# DriverBoard.net
KiCad netlist of a schematic drawn in Altium Designer
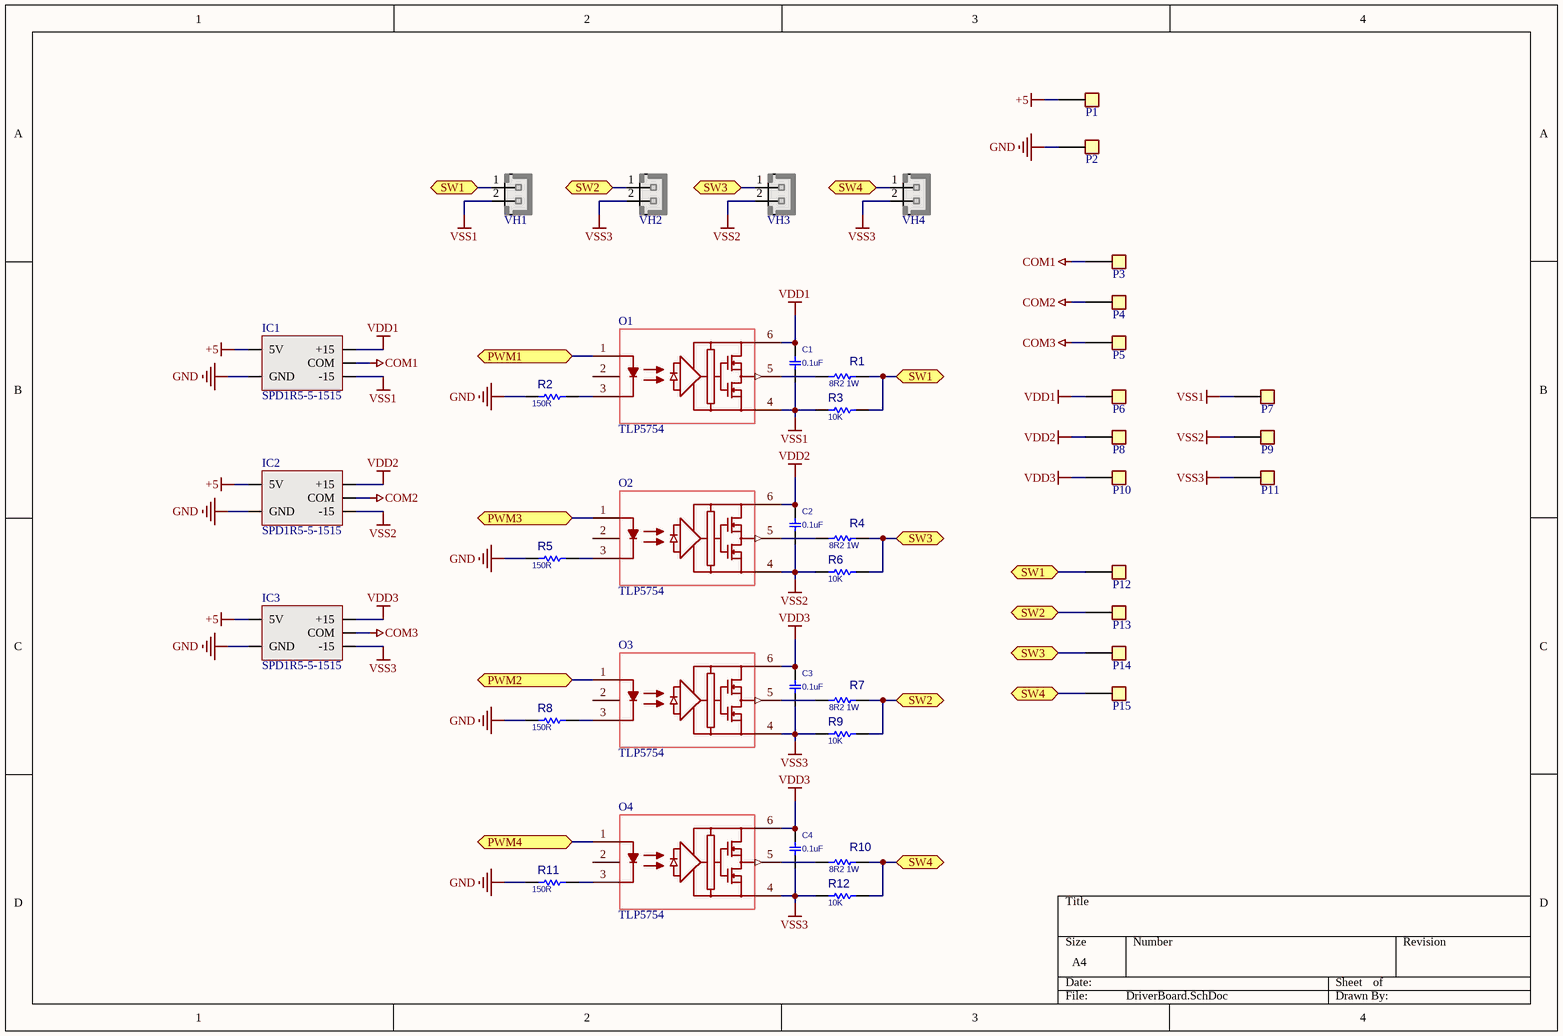
[diagram p0: DriverBoard.SchDoc]

(export (version "E")
  (design (tool "Eeschema 10.0.6"))
  (components
    (comp (ref "C1")
      (value "0.1uF")
      (footprint "cap_0805")
      (description "CAP SMD")
      (fields (field (name "MANF_P#") "MANF_PART#"))
      (libsource (lib "IoT") (part "CAP SMD"))
    )
    (comp (ref "C2")
      (value "0.1uF")
      (footprint "cap_0805")
      (description "CAP SMD")
      (fields (field (name "MANF_P#") "MANF_PART#"))
      (libsource (lib "IoT") (part "CAP SMD"))
    )
    (comp (ref "C3")
      (value "0.1uF")
      (footprint "cap_0805")
      (description "CAP SMD")
      (fields (field (name "MANF_P#") "MANF_PART#"))
      (libsource (lib "IoT") (part "CAP SMD"))
    )
    (comp (ref "C4")
      (value "0.1uF")
      (footprint "cap_0805")
      (description "CAP SMD")
      (fields (field (name "MANF_P#") "MANF_PART#"))
      (libsource (lib "IoT") (part "CAP SMD"))
    )
    (comp (ref "IC1")
      (value "SPD1R5-5-1515")
      (footprint "SPS1R5")
      (description "Power supply Driver SPD1R5-5-1515\r\nEfficiency 80%\r\nInput 0.381A\r\nOutput 50mA")
      (libsource (lib "IoT") (part "SPD1R5-5-1515"))
    )
    (comp (ref "IC2")
      (value "SPD1R5-5-1515")
      (footprint "SPS1R5")
      (description "Power supply Driver SPD1R5-5-1515\r\nEfficiency 80%\r\nInput 0.381A\r\nOutput 50mA")
      (libsource (lib "IoT") (part "SPD1R5-5-1515"))
    )
    (comp (ref "IC3")
      (value "SPD1R5-5-1515")
      (footprint "SPS1R5")
      (description "Power supply Driver SPD1R5-5-1515\r\nEfficiency 80%\r\nInput 0.381A\r\nOutput 50mA")
      (libsource (lib "IoT") (part "SPD1R5-5-1515"))
    )
    (comp (ref "O1")
      (value "TLP5754")
      (footprint "TLP5754")
      (fields (field (name "MF") "Toshiba Semiconductor") (field (name "MP") "TLP250"))
      (libsource (lib "IoT") (part "TLP5754"))
    )
    (comp (ref "O2")
      (value "TLP5754")
      (footprint "TLP5754")
      (fields (field (name "MF") "Toshiba Semiconductor") (field (name "MP") "TLP250"))
      (libsource (lib "IoT") (part "TLP5754"))
    )
    (comp (ref "O3")
      (value "TLP5754")
      (footprint "TLP5754")
      (fields (field (name "MF") "Toshiba Semiconductor") (field (name "MP") "TLP250"))
      (libsource (lib "IoT") (part "TLP5754"))
    )
    (comp (ref "O4")
      (value "TLP5754")
      (footprint "TLP5754")
      (fields (field (name "MF") "Toshiba Semiconductor") (field (name "MP") "TLP250"))
      (libsource (lib "IoT") (part "TLP5754"))
    )
    (comp (ref "P1")
      (value "test PCB")
      (footprint "tp_red_1p")
      (description "testpin")
      (libsource (lib "IoT") (part "test PCB"))
    )
    (comp (ref "P2")
      (value "test PCB")
      (footprint "Tp_black_1p")
      (description "testpin")
      (libsource (lib "IoT") (part "test PCB"))
    )
    (comp (ref "P3")
      (value "test PCB")
      (footprint "tp_white_1p")
      (description "testpin")
      (libsource (lib "IoT") (part "test PCB"))
    )
    (comp (ref "P4")
      (value "test PCB")
      (footprint "tp_white_1p")
      (description "testpin")
      (libsource (lib "IoT") (part "test PCB"))
    )
    (comp (ref "P5")
      (value "test PCB")
      (footprint "tp_white_1p")
      (description "testpin")
      (libsource (lib "IoT") (part "test PCB"))
    )
    (comp (ref "P6")
      (value "test PCB")
      (footprint "tp_red_1p")
      (description "testpin")
      (libsource (lib "IoT") (part "test PCB"))
    )
    (comp (ref "P7")
      (value "test PCB")
      (footprint "Tp_black_1p")
      (description "testpin")
      (libsource (lib "IoT") (part "test PCB"))
    )
    (comp (ref "P8")
      (value "test PCB")
      (footprint "tp_red_1p")
      (description "testpin")
      (libsource (lib "IoT") (part "test PCB"))
    )
    (comp (ref "P9")
      (value "test PCB")
      (footprint "Tp_black_1p")
      (description "testpin")
      (libsource (lib "IoT") (part "test PCB"))
    )
    (comp (ref "P10")
      (value "test PCB")
      (footprint "tp_red_1p")
      (description "testpin")
      (libsource (lib "IoT") (part "test PCB"))
    )
    (comp (ref "P11")
      (value "test PCB")
      (footprint "Tp_black_1p")
      (description "testpin")
      (libsource (lib "IoT") (part "test PCB"))
    )
    (comp (ref "P12")
      (value "test PCB")
      (footprint "Tp_blue_1p")
      (description "testpin")
      (libsource (lib "IoT") (part "test PCB"))
    )
    (comp (ref "P13")
      (value "test PCB")
      (footprint "Tp_blue_1p")
      (description "testpin")
      (libsource (lib "IoT") (part "test PCB"))
    )
    (comp (ref "P14")
      (value "test PCB")
      (footprint "Tp_blue_1p")
      (description "testpin")
      (libsource (lib "IoT") (part "test PCB"))
    )
    (comp (ref "P15")
      (value "test PCB")
      (footprint "Tp_blue_1p")
      (description "testpin")
      (libsource (lib "IoT") (part "test PCB"))
    )
    (comp (ref "R1")
      (value "8R2 1W")
      (footprint "R2512")
      (description "RES SMD")
      (fields (field (name "MANF_P#") "WSLP0805R0100FEA") (field (name "MANF") "VISHAY"))
      (libsource (lib "IoT") (part "RES SMD"))
    )
    (comp (ref "R2")
      (value "150R")
      (footprint "R0805")
      (description "RES SMD")
      (fields (field (name "MANF_P#") "WSLP0805R0100FEA") (field (name "MANF") "VISHAY"))
      (libsource (lib "IoT") (part "RES SMD"))
    )
    (comp (ref "R3")
      (value "10K")
      (footprint "R0805")
      (description "RES SMD")
      (fields (field (name "MANF_P#") "WSLP0805R0100FEA") (field (name "MANF") "VISHAY"))
      (libsource (lib "IoT") (part "RES SMD"))
    )
    (comp (ref "R4")
      (value "8R2 1W")
      (footprint "R2512")
      (description "RES SMD")
      (fields (field (name "MANF_P#") "WSLP0805R0100FEA") (field (name "MANF") "VISHAY"))
      (libsource (lib "IoT") (part "RES SMD"))
    )
    (comp (ref "R5")
      (value "150R")
      (footprint "R0805")
      (description "RES SMD")
      (fields (field (name "MANF_P#") "WSLP0805R0100FEA") (field (name "MANF") "VISHAY"))
      (libsource (lib "IoT") (part "RES SMD"))
    )
    (comp (ref "R6")
      (value "10K")
      (footprint "R0805")
      (description "RES SMD")
      (fields (field (name "MANF_P#") "WSLP0805R0100FEA") (field (name "MANF") "VISHAY"))
      (libsource (lib "IoT") (part "RES SMD"))
    )
    (comp (ref "R7")
      (value "8R2 1W")
      (footprint "R2512")
      (description "RES SMD")
      (fields (field (name "MANF_P#") "WSLP0805R0100FEA") (field (name "MANF") "VISHAY"))
      (libsource (lib "IoT") (part "RES SMD"))
    )
    (comp (ref "R8")
      (value "150R")
      (footprint "R0805")
      (description "RES SMD")
      (fields (field (name "MANF_P#") "WSLP0805R0100FEA") (field (name "MANF") "VISHAY"))
      (libsource (lib "IoT") (part "RES SMD"))
    )
    (comp (ref "R9")
      (value "10K")
      (footprint "R0805")
      (description "RES SMD")
      (fields (field (name "MANF_P#") "WSLP0805R0100FEA") (field (name "MANF") "VISHAY"))
      (libsource (lib "IoT") (part "RES SMD"))
    )
    (comp (ref "R10")
      (value "8R2 1W")
      (footprint "R2512")
      (description "RES SMD")
      (fields (field (name "MANF_P#") "WSLP0805R0100FEA") (field (name "MANF") "VISHAY"))
      (libsource (lib "IoT") (part "RES SMD"))
    )
    (comp (ref "R11")
      (value "150R")
      (footprint "R0805")
      (description "RES SMD")
      (fields (field (name "MANF_P#") "WSLP0805R0100FEA") (field (name "MANF") "VISHAY"))
      (libsource (lib "IoT") (part "RES SMD"))
    )
    (comp (ref "R12")
      (value "10K")
      (footprint "R0805")
      (description "RES SMD")
      (fields (field (name "MANF_P#") "WSLP0805R0100FEA") (field (name "MANF") "VISHAY"))
      (libsource (lib "IoT") (part "RES SMD"))
    )
    (comp (ref "VH1")
      (value "HHDR_2")
      (footprint "VH-2")
      (description "VH-2")
      (libsource (lib "IoT") (part "VH-2"))
    )
    (comp (ref "VH2")
      (value "HHDR_2")
      (footprint "VH-2")
      (description "VH-2")
      (libsource (lib "IoT") (part "VH-2"))
    )
    (comp (ref "VH3")
      (value "HHDR_2")
      (footprint "VH-2")
      (description "VH-2")
      (libsource (lib "IoT") (part "VH-2"))
    )
    (comp (ref "VH4")
      (value "HHDR_2")
      (footprint "VH-2")
      (description "VH-2")
      (libsource (lib "IoT") (part "VH-2"))
    )
  )
  (nets
    (net (code "1") (name "+5") (class "Default")
      (node (ref "IC1") (pin "1") (pinfunction "5V_1") (pintype "passive"))
      (node (ref "IC2") (pin "1") (pinfunction "5V_1") (pintype "passive"))
      (node (ref "IC3") (pin "1") (pinfunction "5V_1") (pintype "passive"))
      (node (ref "P1") (pin "1") (pinfunction "1_1") (pintype "power_in"))
    )
    (net (code "2") (name "/PWM1") (class "Default")
      (node (ref "O1") (pin "1") (pinfunction "NC_1") (pintype "passive"))
    )
    (net (code "3") (name "/PWM2") (class "Default")
      (node (ref "O3") (pin "1") (pinfunction "NC_1") (pintype "passive"))
    )
    (net (code "4") (name "/PWM3") (class "Default")
      (node (ref "O2") (pin "1") (pinfunction "NC_1") (pintype "passive"))
    )
    (net (code "5") (name "/PWM4") (class "Default")
      (node (ref "O4") (pin "1") (pinfunction "NC_1") (pintype "passive"))
    )
    (net (code "6") (name "/SW1") (class "Default")
      (node (ref "P12") (pin "1") (pinfunction "1_1") (pintype "power_in"))
      (node (ref "R1") (pin "2") (pinfunction "2_2") (pintype "passive"))
      (node (ref "R3") (pin "2") (pinfunction "2_2") (pintype "passive"))
      (node (ref "VH1") (pin "1") (pinfunction "1_1") (pintype "passive"))
    )
    (net (code "7") (name "/SW2") (class "Default")
      (node (ref "P13") (pin "1") (pinfunction "1_1") (pintype "power_in"))
      (node (ref "R7") (pin "2") (pinfunction "2_2") (pintype "passive"))
      (node (ref "R9") (pin "2") (pinfunction "2_2") (pintype "passive"))
      (node (ref "VH2") (pin "1") (pinfunction "1_1") (pintype "passive"))
    )
    (net (code "8") (name "/SW3") (class "Default")
      (node (ref "P14") (pin "1") (pinfunction "1_1") (pintype "power_in"))
      (node (ref "R4") (pin "2") (pinfunction "2_2") (pintype "passive"))
      (node (ref "R6") (pin "2") (pinfunction "2_2") (pintype "passive"))
      (node (ref "VH3") (pin "1") (pinfunction "1_1") (pintype "passive"))
    )
    (net (code "9") (name "/SW4") (class "Default")
      (node (ref "P15") (pin "1") (pinfunction "1_1") (pintype "power_in"))
      (node (ref "R10") (pin "2") (pinfunction "2_2") (pintype "passive"))
      (node (ref "R12") (pin "2") (pinfunction "2_2") (pintype "passive"))
      (node (ref "VH4") (pin "1") (pinfunction "1_1") (pintype "passive"))
    )
    (net (code "10") (name "COM1") (class "Default")
      (node (ref "IC1") (pin "4") (pinfunction "COM_4") (pintype "passive"))
      (node (ref "P3") (pin "1") (pinfunction "1_1") (pintype "power_in"))
    )
    (net (code "11") (name "COM2") (class "Default")
      (node (ref "IC2") (pin "4") (pinfunction "COM_4") (pintype "passive"))
      (node (ref "P4") (pin "1") (pinfunction "1_1") (pintype "power_in"))
    )
    (net (code "12") (name "COM3") (class "Default")
      (node (ref "IC3") (pin "4") (pinfunction "COM_4") (pintype "passive"))
      (node (ref "P5") (pin "1") (pinfunction "1_1") (pintype "power_in"))
    )
    (net (code "13") (name "GND") (class "Default")
      (node (ref "IC1") (pin "2") (pinfunction "GND_2") (pintype "passive"))
      (node (ref "IC2") (pin "2") (pinfunction "GND_2") (pintype "passive"))
      (node (ref "IC3") (pin "2") (pinfunction "GND_2") (pintype "passive"))
      (node (ref "P2") (pin "1") (pinfunction "1_1") (pintype "power_in"))
      (node (ref "R11") (pin "1") (pinfunction "1_1") (pintype "passive"))
      (node (ref "R2") (pin "1") (pinfunction "1_1") (pintype "passive"))
      (node (ref "R5") (pin "1") (pinfunction "1_1") (pintype "passive"))
      (node (ref "R8") (pin "1") (pinfunction "1_1") (pintype "passive"))
    )
    (net (code "14") (name "Net-(O1-KATHODE)") (class "Default")
      (node (ref "O1") (pin "3") (pinfunction "KATHODE_3") (pintype "passive"))
      (node (ref "R2") (pin "2") (pinfunction "2_2") (pintype "passive"))
    )
    (net (code "15") (name "Net-(O1-VO)") (class "Default")
      (node (ref "O1") (pin "5") (pinfunction "VO_5") (pintype "output"))
      (node (ref "R1") (pin "1") (pinfunction "1_1") (pintype "passive"))
    )
    (net (code "16") (name "Net-(O2-KATHODE)") (class "Default")
      (node (ref "O2") (pin "3") (pinfunction "KATHODE_3") (pintype "passive"))
      (node (ref "R5") (pin "2") (pinfunction "2_2") (pintype "passive"))
    )
    (net (code "17") (name "Net-(O2-VO)") (class "Default")
      (node (ref "O2") (pin "5") (pinfunction "VO_5") (pintype "output"))
      (node (ref "R4") (pin "1") (pinfunction "1_1") (pintype "passive"))
    )
    (net (code "18") (name "Net-(O3-KATHODE)") (class "Default")
      (node (ref "O3") (pin "3") (pinfunction "KATHODE_3") (pintype "passive"))
      (node (ref "R8") (pin "2") (pinfunction "2_2") (pintype "passive"))
    )
    (net (code "19") (name "Net-(O3-VO)") (class "Default")
      (node (ref "O3") (pin "5") (pinfunction "VO_5") (pintype "output"))
      (node (ref "R7") (pin "1") (pinfunction "1_1") (pintype "passive"))
    )
    (net (code "20") (name "Net-(O4-KATHODE)") (class "Default")
      (node (ref "O4") (pin "3") (pinfunction "KATHODE_3") (pintype "passive"))
      (node (ref "R11") (pin "2") (pinfunction "2_2") (pintype "passive"))
    )
    (net (code "21") (name "Net-(O4-VO)") (class "Default")
      (node (ref "O4") (pin "5") (pinfunction "VO_5") (pintype "output"))
      (node (ref "R10") (pin "1") (pinfunction "1_1") (pintype "passive"))
    )
    (net (code "22") (name "VDD1") (class "Default")
      (node (ref "C1") (pin "2") (pinfunction "2_2") (pintype "passive"))
      (node (ref "IC1") (pin "5") (pinfunction "+15_5") (pintype "passive"))
      (node (ref "O1") (pin "6") (pinfunction "VCC_6") (pintype "power_in"))
      (node (ref "P6") (pin "1") (pinfunction "1_1") (pintype "power_in"))
    )
    (net (code "23") (name "VDD2") (class "Default")
      (node (ref "C2") (pin "2") (pinfunction "2_2") (pintype "passive"))
      (node (ref "IC2") (pin "5") (pinfunction "+15_5") (pintype "passive"))
      (node (ref "O2") (pin "6") (pinfunction "VCC_6") (pintype "power_in"))
      (node (ref "P8") (pin "1") (pinfunction "1_1") (pintype "power_in"))
    )
    (net (code "24") (name "VDD3") (class "Default")
      (node (ref "C3") (pin "2") (pinfunction "2_2") (pintype "passive"))
      (node (ref "C4") (pin "2") (pinfunction "2_2") (pintype "passive"))
      (node (ref "IC3") (pin "5") (pinfunction "+15_5") (pintype "passive"))
      (node (ref "O3") (pin "6") (pinfunction "VCC_6") (pintype "power_in"))
      (node (ref "O4") (pin "6") (pinfunction "VCC_6") (pintype "power_in"))
      (node (ref "P10") (pin "1") (pinfunction "1_1") (pintype "power_in"))
    )
    (net (code "25") (name "VSS1") (class "Default")
      (node (ref "C1") (pin "1") (pinfunction "1_1") (pintype "passive"))
      (node (ref "IC1") (pin "3") (pinfunction "-15_3") (pintype "passive"))
      (node (ref "O1") (pin "4") (pinfunction "GND_4") (pintype "power_in"))
      (node (ref "P7") (pin "1") (pinfunction "1_1") (pintype "power_in"))
      (node (ref "R3") (pin "1") (pinfunction "1_1") (pintype "passive"))
      (node (ref "VH1") (pin "2") (pinfunction "2_2") (pintype "passive"))
    )
    (net (code "26") (name "VSS2") (class "Default")
      (node (ref "C2") (pin "1") (pinfunction "1_1") (pintype "passive"))
      (node (ref "IC2") (pin "3") (pinfunction "-15_3") (pintype "passive"))
      (node (ref "O2") (pin "4") (pinfunction "GND_4") (pintype "power_in"))
      (node (ref "P9") (pin "1") (pinfunction "1_1") (pintype "power_in"))
      (node (ref "R6") (pin "1") (pinfunction "1_1") (pintype "passive"))
      (node (ref "VH3") (pin "2") (pinfunction "2_2") (pintype "passive"))
    )
    (net (code "27") (name "VSS3") (class "Default")
      (node (ref "C3") (pin "1") (pinfunction "1_1") (pintype "passive"))
      (node (ref "C4") (pin "1") (pinfunction "1_1") (pintype "passive"))
      (node (ref "IC3") (pin "3") (pinfunction "-15_3") (pintype "passive"))
      (node (ref "O3") (pin "4") (pinfunction "GND_4") (pintype "power_in"))
      (node (ref "O4") (pin "4") (pinfunction "GND_4") (pintype "power_in"))
      (node (ref "P11") (pin "1") (pinfunction "1_1") (pintype "power_in"))
      (node (ref "R12") (pin "1") (pinfunction "1_1") (pintype "passive"))
      (node (ref "R9") (pin "1") (pinfunction "1_1") (pintype "passive"))
      (node (ref "VH2") (pin "2") (pinfunction "2_2") (pintype "passive"))
      (node (ref "VH4") (pin "2") (pinfunction "2_2") (pintype "passive"))
    )
    (net (code "28") (name "unconnected-(O1-ANODE-Pad2)") (class "Default")
      (node (ref "O1") (pin "2") (pinfunction "ANODE_2") (pintype "passive"))
    )
    (net (code "29") (name "unconnected-(O2-ANODE-Pad2)") (class "Default")
      (node (ref "O2") (pin "2") (pinfunction "ANODE_2") (pintype "passive"))
    )
    (net (code "30") (name "unconnected-(O3-ANODE-Pad2)") (class "Default")
      (node (ref "O3") (pin "2") (pinfunction "ANODE_2") (pintype "passive"))
    )
    (net (code "31") (name "unconnected-(O4-ANODE-Pad2)") (class "Default")
      (node (ref "O4") (pin "2") (pinfunction "ANODE_2") (pintype "passive"))
    )
  )
)
